# MQ.net
KiCad netlist of a schematic drawn in Altium Designer
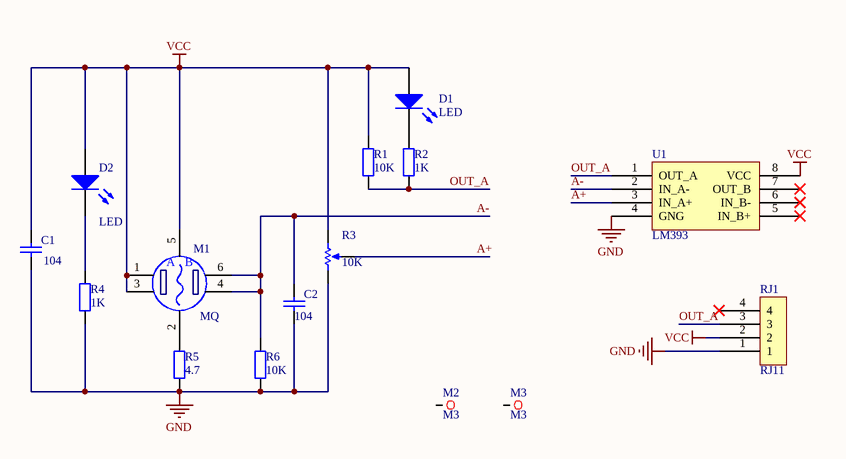
[diagram p0: MQ.SchDoc]

(export (version "E")
  (design (tool "Eeschema 10.0.6"))
  (components
    (comp (ref "C1")
      (value "104")
      (footprint "0603_C")
      (description "Capacitor")
      (fields (field (name "Comment") "Cap") (field (name "PUBLISHER") "Altium Limited"))
      (libsource (lib "Miscellaneous Devices") (part "Cap"))
    )
    (comp (ref "C2")
      (value "104")
      (footprint "0603_C")
      (description "Capacitor")
      (fields (field (name "Comment") "Cap") (field (name "PUBLISHER") "Altium Limited"))
      (libsource (lib "Miscellaneous Devices") (part "Cap"))
    )
    (comp (ref "D1")
      (value "LED")
      (footprint "0805")
      (description "Typical RED GaAs LED")
      (fields (field (name "PUBLISHER") "Altium Limited"))
      (libsource (lib "Miscellaneous Devices") (part "LED1"))
    )
    (comp (ref "D2")
      (value "LED")
      (footprint "0805")
      (description "Typical RED GaAs LED")
      (fields (field (name "PUBLISHER") "Altium Limited"))
      (libsource (lib "Miscellaneous Devices") (part "LED1"))
    )
    (comp (ref "M1") (value "MQ") (footprint "MQ") (libsource (lib "MQ") (part "MQ")))
    (comp (ref "M2") (value "M3") (footprint "M3") (libsource (lib "QQW-1.SCHLIB") (part "M3")))
    (comp (ref "M3") (value "M3") (footprint "M3") (libsource (lib "QQW-1.SCHLIB") (part "M3")))
    (comp (ref "R1")
      (value "10K")
      (footprint "0603_R")
      (description "Resistor")
      (fields (field (name "Comment") "Res2") (field (name "PUBLISHER") "Altium Limited"))
      (libsource (lib "Miscellaneous Devices") (part "Res2"))
    )
    (comp (ref "R2")
      (value "1K")
      (footprint "0603_R")
      (description "Resistor")
      (fields (field (name "Comment") "Res2") (field (name "PUBLISHER") "Altium Limited"))
      (libsource (lib "Miscellaneous Devices") (part "Res2"))
    )
    (comp (ref "R3")
      (value "10K")
      (footprint "电位器")
      (description "Potentiometer")
      (fields (field (name "Comment") "RPot") (field (name "PUBLISHER") "Altium Limited"))
      (libsource (lib "Miscellaneous Devices") (part "RPot"))
    )
    (comp (ref "R4")
      (value "1K")
      (footprint "0603_R")
      (description "Resistor")
      (fields (field (name "Comment") "Res2") (field (name "PUBLISHER") "Altium Limited"))
      (libsource (lib "Miscellaneous Devices") (part "Res2"))
    )
    (comp (ref "R5")
      (value "4.7")
      (footprint "0603_R")
      (description "Resistor")
      (fields (field (name "Comment") "Res2") (field (name "PUBLISHER") "Altium Limited"))
      (libsource (lib "Miscellaneous Devices") (part "Res2"))
    )
    (comp (ref "R6")
      (value "10K")
      (footprint "0603_R")
      (description "Resistor")
      (fields (field (name "Comment") "Res2") (field (name "PUBLISHER") "Altium Limited"))
      (libsource (lib "Miscellaneous Devices") (part "Res2"))
    )
    (comp (ref "RJ1") (value "RJ11") (footprint "RJ11") (libsource (lib "少儿智能车") (part "RJ11")))
    (comp (ref "U1") (value "LM393") (footprint "SO-8") (libsource (lib "Infrared") (part "LM393")))
  )
  (nets
    (net (code "1") (name "/A+") (class "Default")
      (node (ref "R3") (pin "3") (pinfunction "TAP_3") (pintype "passive"))
      (node (ref "U1") (pin "3") (pinfunction "IN_A+_3") (pintype "passive"))
    )
    (net (code "2") (name "/A-") (class "Default")
      (node (ref "C2") (pin "2") (pinfunction "2_2") (pintype "passive"))
      (node (ref "M1") (pin "4") (pinfunction "4_4") (pintype "passive"))
      (node (ref "M1") (pin "6") (pinfunction "6_6") (pintype "passive"))
      (node (ref "R6") (pin "2") (pinfunction "2_2") (pintype "passive"))
      (node (ref "U1") (pin "2") (pinfunction "IN_A-_2") (pintype "passive"))
    )
    (net (code "3") (name "/OUT_A") (class "Default")
      (node (ref "R1") (pin "1") (pinfunction "1_1") (pintype "passive"))
      (node (ref "R2") (pin "1") (pinfunction "1_1") (pintype "passive"))
      (node (ref "RJ1") (pin "3") (pinfunction "3_3") (pintype "passive"))
      (node (ref "U1") (pin "1") (pinfunction "OUT_A_1") (pintype "passive"))
    )
    (net (code "4") (name "GND") (class "Default")
      (node (ref "C1") (pin "1") (pinfunction "1_1") (pintype "passive"))
      (node (ref "C2") (pin "1") (pinfunction "1_1") (pintype "passive"))
      (node (ref "R3") (pin "1") (pinfunction "TOP_1") (pintype "passive"))
      (node (ref "R4") (pin "1") (pinfunction "1_1") (pintype "passive"))
      (node (ref "R5") (pin "1") (pinfunction "1_1") (pintype "passive"))
      (node (ref "R6") (pin "1") (pinfunction "1_1") (pintype "passive"))
      (node (ref "RJ1") (pin "1") (pinfunction "1_1") (pintype "passive"))
      (node (ref "U1") (pin "4") (pinfunction "GNG_4") (pintype "passive"))
    )
    (net (code "5") (name "Net-(D1-K)") (class "Default")
      (node (ref "D1") (pin "2") (pinfunction "K_2") (pintype "passive"))
      (node (ref "R2") (pin "2") (pinfunction "2_2") (pintype "passive"))
    )
    (net (code "6") (name "Net-(D2-K)") (class "Default")
      (node (ref "D2") (pin "2") (pinfunction "K_2") (pintype "passive"))
      (node (ref "R4") (pin "2") (pinfunction "2_2") (pintype "passive"))
    )
    (net (code "7") (name "Net-(M1-Pad2)") (class "Default")
      (node (ref "M1") (pin "2") (pinfunction "2_2") (pintype "passive"))
      (node (ref "R5") (pin "2") (pinfunction "2_2") (pintype "passive"))
    )
    (net (code "8") (name "VCC") (class "Default")
      (node (ref "C1") (pin "2") (pinfunction "2_2") (pintype "passive"))
      (node (ref "D1") (pin "1") (pinfunction "A_1") (pintype "passive"))
      (node (ref "D2") (pin "1") (pinfunction "A_1") (pintype "passive"))
      (node (ref "M1") (pin "1") (pinfunction "1_1") (pintype "passive"))
      (node (ref "M1") (pin "3") (pinfunction "3_3") (pintype "passive"))
      (node (ref "M1") (pin "5") (pinfunction "5_5") (pintype "passive"))
      (node (ref "R1") (pin "2") (pinfunction "2_2") (pintype "passive"))
      (node (ref "R3") (pin "2") (pinfunction "BOT_2") (pintype "passive"))
      (node (ref "RJ1") (pin "2") (pinfunction "2_2") (pintype "passive"))
      (node (ref "U1") (pin "8") (pinfunction "VCC_8") (pintype "passive"))
    )
    (net (code "9") (name "unconnected-(M2-Pad0)") (class "Default")
      (node (ref "M2") (pin "0") (pinfunction "0_0") (pintype "passive"))
    )
    (net (code "10") (name "unconnected-(M3-Pad0)") (class "Default")
      (node (ref "M3") (pin "0") (pinfunction "0_0") (pintype "passive"))
    )
    (net (code "11") (name "unconnected-(RJ1-Pad4)") (class "Default")
      (node (ref "RJ1") (pin "4") (pinfunction "4_4") (pintype "passive+no_connect"))
    )
    (net (code "12") (name "unconnected-(U1-IN_B+-Pad5)") (class "Default")
      (node (ref "U1") (pin "5") (pinfunction "IN_B+_5") (pintype "passive+no_connect"))
    )
    (net (code "13") (name "unconnected-(U1-IN_B--Pad6)") (class "Default")
      (node (ref "U1") (pin "6") (pinfunction "IN_B-_6") (pintype "passive+no_connect"))
    )
    (net (code "14") (name "unconnected-(U1-OUT_B-Pad7)") (class "Default")
      (node (ref "U1") (pin "7") (pinfunction "OUT_B_7") (pintype "passive+no_connect"))
    )
  )
)
